# Envelope.net
KiCad netlist of a schematic drawn in EAGLE
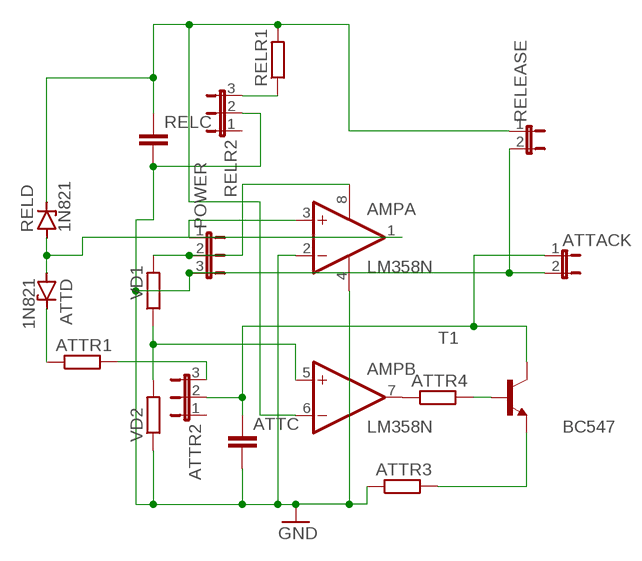
[diagram p0: schematic, sheet 1]

(export (version "E")
  (design (tool "Eeschema 10.0.6"))
  (components
    (comp (ref "AMP")
      (value "LM358N")
      (footprint "eagle-import:DIL08")
      (libsource (lib "eagle-import") (part "LM358N"))
    )
    (comp (ref "ATTACK")
      (value "JP1E")
      (footprint "eagle-import:JP1")
      (libsource (lib "eagle-import") (part "JP1E"))
    )
    (comp (ref "ATTC")
      (value "C-EU025-025X050")
      (footprint "eagle-import:C025-025X050")
      (libsource (lib "eagle-import") (part "C-EU025-025X050"))
    )
    (comp (ref "ATTD")
      (value "1N821")
      (footprint "eagle-import:DO35Z10")
      (libsource (lib "eagle-import") (part "1N821"))
    )
    (comp (ref "ATTR1")
      (value "R-EU_0207/10")
      (footprint "eagle-import:0207_10")
      (libsource (lib "eagle-import") (part "R-EU_0207/10"))
    )
    (comp (ref "ATTR2")
      (value "JP2E")
      (footprint "eagle-import:JP2")
      (libsource (lib "eagle-import") (part "JP2E"))
    )
    (comp (ref "ATTR3")
      (value "R-EU_0207/10")
      (footprint "eagle-import:0207_10")
      (libsource (lib "eagle-import") (part "R-EU_0207/10"))
    )
    (comp (ref "ATTR4")
      (value "R-EU_0207/10")
      (footprint "eagle-import:0207_10")
      (libsource (lib "eagle-import") (part "R-EU_0207/10"))
    )
    (comp (ref "POWER")
      (value "JP2E")
      (footprint "eagle-import:JP2")
      (libsource (lib "eagle-import") (part "JP2E"))
    )
    (comp (ref "RELC")
      (value "C-EU025-025X050")
      (footprint "eagle-import:C025-025X050")
      (libsource (lib "eagle-import") (part "C-EU025-025X050"))
    )
    (comp (ref "RELD")
      (value "1N821")
      (footprint "eagle-import:DO35Z10")
      (libsource (lib "eagle-import") (part "1N821"))
    )
    (comp (ref "RELEASE")
      (value "JP1E")
      (footprint "eagle-import:JP1")
      (libsource (lib "eagle-import") (part "JP1E"))
    )
    (comp (ref "RELR1")
      (value "R-EU_0207/10")
      (footprint "eagle-import:0207_10")
      (libsource (lib "eagle-import") (part "R-EU_0207/10"))
    )
    (comp (ref "RELR2")
      (value "JP2E")
      (footprint "eagle-import:JP2")
      (libsource (lib "eagle-import") (part "JP2E"))
    )
    (comp (ref "T1")
      (value "BC547")
      (footprint "eagle-import:TO92")
      (libsource (lib "eagle-import") (part "BC547"))
    )
    (comp (ref "VD1")
      (value "R-EU_0207/10")
      (footprint "eagle-import:0207_10")
      (libsource (lib "eagle-import") (part "R-EU_0207/10"))
    )
    (comp (ref "VD2")
      (value "R-EU_0207/10")
      (footprint "eagle-import:0207_10")
      (libsource (lib "eagle-import") (part "R-EU_0207/10"))
    )
  )
  (nets
    (net (code "1") (name "GND") (class "Default")
      (node (ref "AMP") (pin "2") (pinfunction "-IN_2") (pintype "input"))
      (node (ref "AMP") (pin "4") (pinfunction "V-_4") (pintype "power_in"))
      (node (ref "ATTACK") (pin "2") (pinfunction "2_2") (pintype "passive"))
      (node (ref "ATTC") (pin "2") (pinfunction "2_2") (pintype "passive"))
      (node (ref "ATTR3") (pin "1") (pinfunction "1_1") (pintype "passive"))
      (node (ref "POWER") (pin "3") (pinfunction "3_3") (pintype "passive"))
      (node (ref "RELC") (pin "2") (pinfunction "2_2") (pintype "passive"))
      (node (ref "RELEASE") (pin "2") (pinfunction "2_2") (pintype "passive"))
      (node (ref "RELR2") (pin "2") (pinfunction "2_2") (pintype "passive"))
      (node (ref "VD2") (pin "1") (pinfunction "1_1") (pintype "passive"))
    )
    (net (code "2") (name "Net-(AMPA-+IN)") (class "Default")
      (node (ref "AMP") (pin "3") (pinfunction "+IN_3") (pintype "input"))
      (node (ref "POWER") (pin "1") (pinfunction "1_1") (pintype "passive"))
    )
    (net (code "3") (name "Net-(AMPA-OUT)") (class "Default")
      (node (ref "AMP") (pin "1") (pinfunction "OUT_1") (pintype "output"))
      (node (ref "ATTD") (pin "A") (pinfunction "A_A") (pintype "passive"))
      (node (ref "RELD") (pin "A") (pinfunction "A_A") (pintype "passive"))
    )
    (net (code "4") (name "Net-(AMPB-+IN)") (class "Default")
      (node (ref "AMP") (pin "5") (pinfunction "+IN_5") (pintype "input"))
      (node (ref "VD1") (pin "1") (pinfunction "1_1") (pintype "passive"))
      (node (ref "VD2") (pin "2") (pinfunction "2_2") (pintype "passive"))
    )
    (net (code "5") (name "Net-(AMPB--IN)") (class "Default")
      (node (ref "AMP") (pin "6") (pinfunction "-IN_6") (pintype "input"))
      (node (ref "RELC") (pin "1") (pinfunction "1_1") (pintype "passive"))
      (node (ref "RELD") (pin "C") (pinfunction "C_C") (pintype "passive"))
      (node (ref "RELEASE") (pin "1") (pinfunction "1_1") (pintype "passive"))
      (node (ref "RELR1") (pin "2") (pinfunction "2_2") (pintype "passive"))
    )
    (net (code "6") (name "Net-(AMPB-OUT)") (class "Default")
      (node (ref "AMP") (pin "7") (pinfunction "OUT_7") (pintype "output"))
      (node (ref "ATTR4") (pin "1") (pinfunction "1_1") (pintype "passive"))
    )
    (net (code "7") (name "Net-(AMPC-V+)") (class "Default")
      (node (ref "AMP") (pin "8") (pinfunction "V+_8") (pintype "power_in"))
      (node (ref "POWER") (pin "2") (pinfunction "2_2") (pintype "passive"))
      (node (ref "VD1") (pin "2") (pinfunction "2_2") (pintype "passive"))
    )
    (net (code "8") (name "Net-(ATTD-PadC)") (class "Default")
      (node (ref "ATTD") (pin "C") (pinfunction "C_C") (pintype "passive"))
      (node (ref "ATTR1") (pin "1") (pinfunction "1_1") (pintype "passive"))
    )
    (net (code "9") (name "Net-(ATTR1-Pad2)") (class "Default")
      (node (ref "ATTR1") (pin "2") (pinfunction "2_2") (pintype "passive"))
      (node (ref "ATTR2") (pin "3") (pinfunction "3_3") (pintype "passive"))
    )
    (net (code "10") (name "Net-(RELR1-Pad1)") (class "Default")
      (node (ref "RELR1") (pin "1") (pinfunction "1_1") (pintype "passive"))
      (node (ref "RELR2") (pin "3") (pinfunction "3_3") (pintype "passive"))
    )
    (net (code "11") (name "Net-(T1-B)") (class "Default")
      (node (ref "ATTR4") (pin "2") (pinfunction "2_2") (pintype "passive"))
      (node (ref "T1") (pin "2") (pinfunction "B_2") (pintype "passive"))
    )
    (net (code "12") (name "Net-(T1-C)") (class "Default")
      (node (ref "ATTACK") (pin "1") (pinfunction "1_1") (pintype "passive"))
      (node (ref "ATTC") (pin "1") (pinfunction "1_1") (pintype "passive"))
      (node (ref "ATTR2") (pin "2") (pinfunction "2_2") (pintype "passive"))
      (node (ref "T1") (pin "3") (pinfunction "C_3") (pintype "passive"))
    )
    (net (code "13") (name "Net-(T1-E)") (class "Default")
      (node (ref "ATTR3") (pin "2") (pinfunction "2_2") (pintype "passive"))
      (node (ref "T1") (pin "1") (pinfunction "E_1") (pintype "passive"))
    )
    (net (code "14") (name "unconnected-(ATTR2-Pad1)") (class "Default")
      (node (ref "ATTR2") (pin "1") (pinfunction "1_1") (pintype "passive"))
    )
    (net (code "15") (name "unconnected-(RELR2-Pad1)") (class "Default")
      (node (ref "RELR2") (pin "1") (pinfunction "1_1") (pintype "passive"))
    )
  )
)
